# Valve.net
KiCad netlist of a schematic drawn in Altium Designer
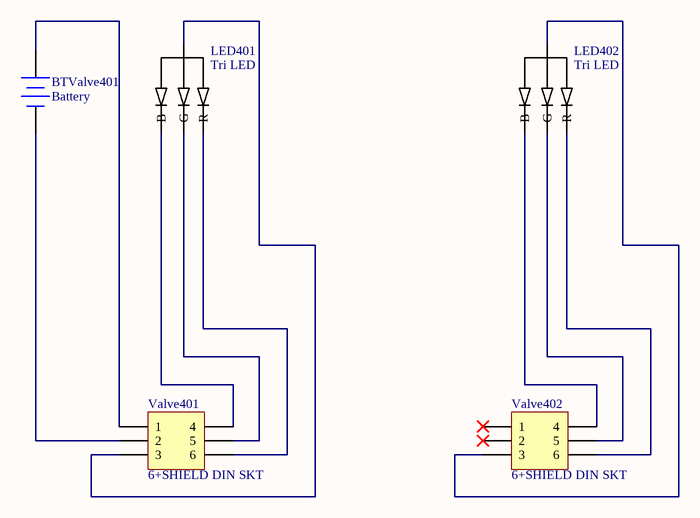
[diagram p0: Valve.SchDoc]

(export (version "E")
  (design (tool "Eeschema 10.0.6"))
  (components
    (comp (ref "BTValve401")
      (value "Battery")
      (footprint "BAT-2")
      (description "Multicell Battery")
      (fields (field (name "PUBLISHER") "Altium Limited"))
      (libsource (lib "Miscellaneous Devices") (part "Battery"))
    )
    (comp (ref "LED401")
      (value "Tri LED")
      (footprint "CLV1A-FKB")
      (libsource (lib "Schlib1") (part "Tri LED"))
    )
    (comp (ref "LED402")
      (value "Tri LED")
      (footprint "CLV1A-FKB")
      (libsource (lib "Schlib1") (part "Tri LED"))
    )
    (comp (ref "Valve401")
      (value "6+SHIELD DIN SKT")
      (footprint "Valve male")
      (description "Header, 3-Pin, Dual row")
      (fields (field (name "PUBLISHER") "Altium Limited"))
      (libsource (lib "Miscellaneous Connectors") (part "Header 3X2A"))
    )
    (comp (ref "Valve402")
      (value "6+SHIELD DIN SKT")
      (footprint "Valve male")
      (description "Header, 3-Pin, Dual row")
      (fields (field (name "PUBLISHER") "Altium Limited"))
      (libsource (lib "Miscellaneous Connectors") (part "Header 3X2A"))
    )
  )
  (nets
    (net (code "1") (name "Net-(BTValve401-+)") (class "Default")
      (node (ref "BTValve401") (pin "1") (pinfunction "+_1") (pintype "passive"))
      (node (ref "Valve401") (pin "1") (pinfunction "1_1") (pintype "passive"))
    )
    (net (code "2") (name "Net-(BTValve401--)") (class "Default")
      (node (ref "BTValve401") (pin "2") (pinfunction "-_2") (pintype "passive"))
      (node (ref "Valve401") (pin "2") (pinfunction "2_2") (pintype "passive"))
    )
    (net (code "3") (name "Net-(LED401-B)") (class "Default")
      (node (ref "LED401") (pin "3") (pinfunction "B_3") (pintype "passive"))
      (node (ref "Valve401") (pin "4") (pinfunction "4_4") (pintype "passive"))
    )
    (net (code "4") (name "Net-(LED401-Common)") (class "Default")
      (node (ref "LED401") (pin "2") (pinfunction "Common_2") (pintype "passive"))
      (node (ref "Valve401") (pin "3") (pinfunction "3_3") (pintype "passive"))
    )
    (net (code "5") (name "Net-(LED401-G)") (class "Default")
      (node (ref "LED401") (pin "4") (pinfunction "G_4") (pintype "passive"))
      (node (ref "Valve401") (pin "5") (pinfunction "5_5") (pintype "passive"))
    )
    (net (code "6") (name "Net-(LED401-R)") (class "Default")
      (node (ref "LED401") (pin "1") (pinfunction "R_1") (pintype "passive"))
      (node (ref "Valve401") (pin "6") (pinfunction "6_6") (pintype "passive"))
    )
    (net (code "7") (name "Net-(LED402-B)") (class "Default")
      (node (ref "LED402") (pin "3") (pinfunction "B_3") (pintype "passive"))
      (node (ref "Valve402") (pin "4") (pinfunction "4_4") (pintype "passive"))
    )
    (net (code "8") (name "Net-(LED402-Common)") (class "Default")
      (node (ref "LED402") (pin "2") (pinfunction "Common_2") (pintype "passive"))
      (node (ref "Valve402") (pin "3") (pinfunction "3_3") (pintype "passive"))
    )
    (net (code "9") (name "Net-(LED402-G)") (class "Default")
      (node (ref "LED402") (pin "4") (pinfunction "G_4") (pintype "passive"))
      (node (ref "Valve402") (pin "5") (pinfunction "5_5") (pintype "passive"))
    )
    (net (code "10") (name "Net-(LED402-R)") (class "Default")
      (node (ref "LED402") (pin "1") (pinfunction "R_1") (pintype "passive"))
      (node (ref "Valve402") (pin "6") (pinfunction "6_6") (pintype "passive"))
    )
    (net (code "11") (name "unconnected-(Valve402-Pad1)") (class "Default")
      (node (ref "Valve402") (pin "1") (pinfunction "1_1") (pintype "passive+no_connect"))
    )
    (net (code "12") (name "unconnected-(Valve402-Pad2)") (class "Default")
      (node (ref "Valve402") (pin "2") (pinfunction "2_2") (pintype "passive+no_connect"))
    )
  )
)
